# SWD.net
KiCad netlist of a schematic drawn in Altium Designer
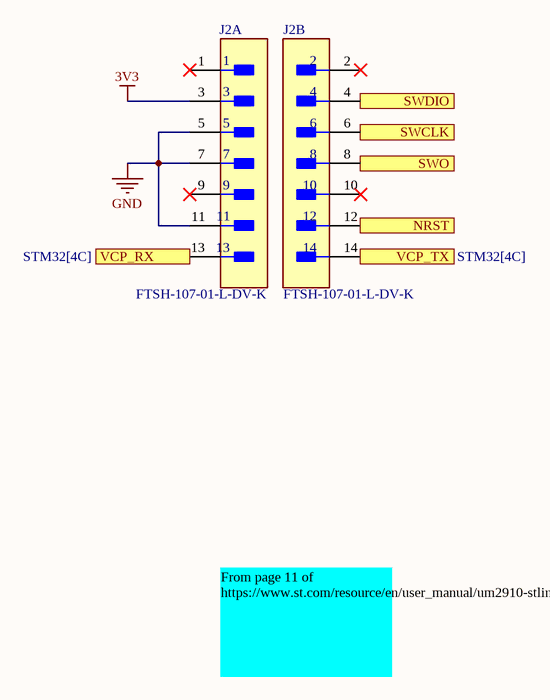
[diagram p0: SWD.SchDoc]

(export (version "E")
  (design (tool "Eeschema 10.0.6"))
  (components
    (comp (ref "J2")
      (value "FTSH-107-01-L-DV-K")
      (footprint "FP-FTSH-107-01-L-DV-K-MFG")
      (description "CONN HEADER SMD 14POS 1.27MM")
      (libsource (lib "Altium Content Vault") (part "7644e1a88aa4da17242a9b8d8257442"))
    )
  )
  (nets
    (net (code "1") (name "/NRST") (class "Default")
      (node (ref "J2") (pin "12") (pinfunction "12_12") (pintype "passive"))
    )
    (net (code "2") (name "/SWCLK") (class "Default")
      (node (ref "J2") (pin "6") (pinfunction "6_6") (pintype "passive"))
    )
    (net (code "3") (name "/SWDIO") (class "Default")
      (node (ref "J2") (pin "4") (pinfunction "4_4") (pintype "passive"))
    )
    (net (code "4") (name "/SWO") (class "Default")
      (node (ref "J2") (pin "8") (pinfunction "8_8") (pintype "passive"))
    )
    (net (code "5") (name "/VCP_RX") (class "Default")
      (node (ref "J2") (pin "13") (pinfunction "13_13") (pintype "passive"))
    )
    (net (code "6") (name "/VCP_TX") (class "Default")
      (node (ref "J2") (pin "14") (pinfunction "14_14") (pintype "passive"))
    )
    (net (code "7") (name "3V3") (class "Default")
      (node (ref "J2") (pin "3") (pinfunction "3_3") (pintype "passive"))
    )
    (net (code "8") (name "GND") (class "Default")
      (node (ref "J2") (pin "11") (pinfunction "11_11") (pintype "passive"))
      (node (ref "J2") (pin "5") (pinfunction "5_5") (pintype "passive"))
      (node (ref "J2") (pin "7") (pinfunction "7_7") (pintype "passive"))
    )
    (net (code "9") (name "unconnected-(J2-Pad1)") (class "Default")
      (node (ref "J2") (pin "1") (pinfunction "1_1") (pintype "passive+no_connect"))
    )
    (net (code "10") (name "unconnected-(J2-Pad2)") (class "Default")
      (node (ref "J2") (pin "2") (pinfunction "2_2") (pintype "passive+no_connect"))
    )
    (net (code "11") (name "unconnected-(J2-Pad9)") (class "Default")
      (node (ref "J2") (pin "9") (pinfunction "9_9") (pintype "passive+no_connect"))
    )
    (net (code "12") (name "unconnected-(J2-Pad10)") (class "Default")
      (node (ref "J2") (pin "10") (pinfunction "10_10") (pintype "passive+no_connect"))
    )
  )
)
